# driver-power-stage.net
KiCad netlist of a schematic drawn in Altium Designer
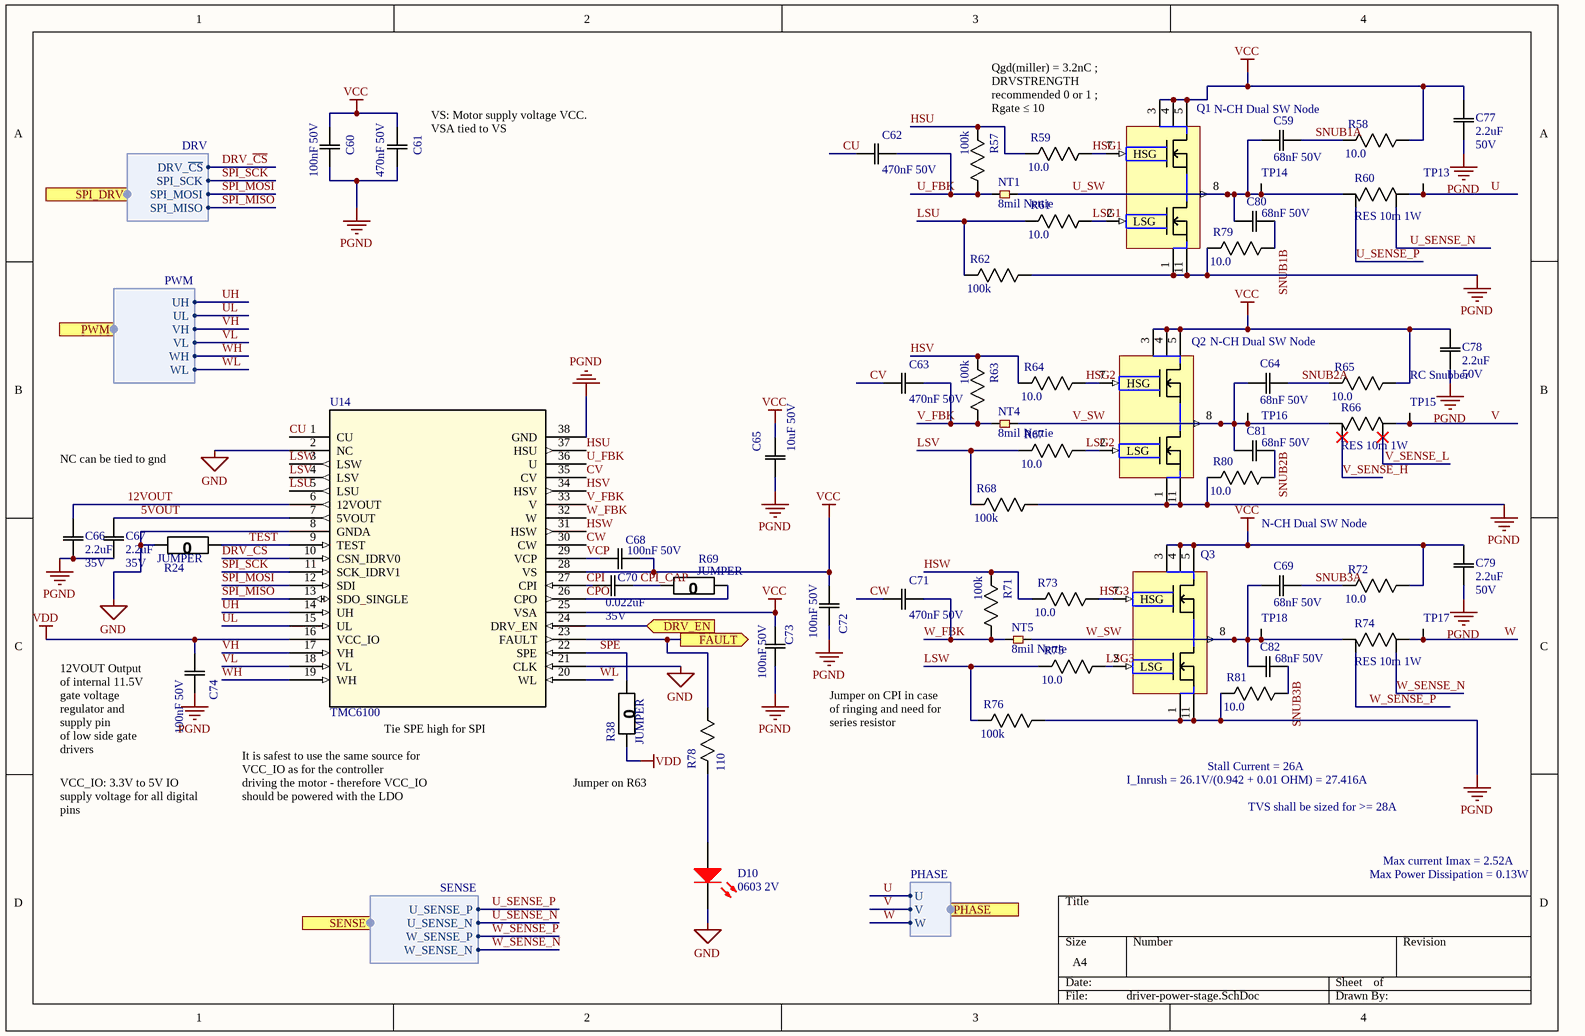
[diagram p0: driver-power-stage.SchDoc]

(export (version "E")
  (design (tool "Eeschema 10.0.6"))
  (components
    (comp (ref "C59")
      (value "68nF 50V")
      (footprint "0603")
      (description "Default Symbol for Capacitors")
      (fields (field (name "PART NUMBER") "CAP 0.068uF 50V") (field (name "TOLERANCE") "10%"))
      (libsource (lib "capacitor_library") (part "CAP_Default"))
    )
    (comp (ref "C60")
      (value "100nF 50V")
      (footprint "0603")
      (description "Default Symbol for Capacitors")
      (fields (field (name "TOLERANCE") "10%") (field (name "PART NUMBER") "CAP 100nF 50V"))
      (libsource (lib "capacitor_library") (part "CAP_Default"))
    )
    (comp (ref "C61")
      (value "470nF 50V")
      (footprint "0603")
      (description "Default Symbol for Capacitors")
      (fields (field (name "TOLERANCE") "10%") (field (name "PART NUMBER") "CAP 470nF 50V"))
      (libsource (lib "capacitor_library") (part "CAP_Default"))
    )
    (comp (ref "C62")
      (value "470nF 50V")
      (footprint "0603")
      (description "Default Symbol for Capacitors")
      (fields (field (name "TOLERANCE") "10%") (field (name "PART NUMBER") "CAP 470nF 50V"))
      (libsource (lib "capacitor_library") (part "CAP_Default"))
    )
    (comp (ref "C63")
      (value "470nF 50V")
      (footprint "0603")
      (description "Default Symbol for Capacitors")
      (fields (field (name "TOLERANCE") "10%") (field (name "PART NUMBER") "CAP 470nF 50V"))
      (libsource (lib "capacitor_library") (part "CAP_Default"))
    )
    (comp (ref "C64")
      (value "68nF 50V")
      (footprint "0603")
      (description "Default Symbol for Capacitors")
      (fields (field (name "PART NUMBER") "CAP 0.068uF 50V") (field (name "TOLERANCE") "10%"))
      (libsource (lib "capacitor_library") (part "CAP_Default"))
    )
    (comp (ref "C65")
      (value "10uF 50V")
      (footprint "0805")
      (description "Default Symbol for Capacitors")
      (fields (field (name "TOLERANCE") "10%") (field (name "PART NUMBER") "CAP 10uF 50V"))
      (libsource (lib "capacitor_library") (part "CAP_Default"))
    )
    (comp (ref "C66")
      (value "2.2uF")
      (footprint "0603")
      (description "Default Symbol for Capacitors")
      (fields
        (field (name "TOLERANCE") "10%")
        (field (name "RATING") "35V")
        (field (name "PART NUMBER") "CAP 2.2uF 35V")
      )
      (libsource (lib "capacitor_library") (part "CAP_Default"))
    )
    (comp (ref "C67")
      (value "2.2uF")
      (footprint "0603")
      (description "Default Symbol for Capacitors")
      (fields
        (field (name "TOLERANCE") "10%")
        (field (name "RATING") "35V")
        (field (name "PART NUMBER") "CAP 2.2uF 35V")
      )
      (libsource (lib "capacitor_library") (part "CAP_Default"))
    )
    (comp (ref "C68")
      (value "100nF 50V")
      (footprint "0603")
      (description "Default Symbol for Capacitors")
      (fields (field (name "TOLERANCE") "10%") (field (name "PART NUMBER") "CAP 100nF 50V"))
      (libsource (lib "capacitor_library") (part "CAP_Default"))
    )
    (comp (ref "C69")
      (value "68nF 50V")
      (footprint "0603")
      (description "Default Symbol for Capacitors")
      (fields (field (name "PART NUMBER") "CAP 0.068uF 50V") (field (name "TOLERANCE") "10%"))
      (libsource (lib "capacitor_library") (part "CAP_Default"))
    )
    (comp (ref "C70")
      (value "0.022uF")
      (footprint "0603")
      (description "Default Symbol for Capacitors")
      (fields
        (field (name "TOLERANCE") "10%")
        (field (name "RATING") "35V")
        (field (name "PART NUMBER") "CAP 0.022uF 35V")
      )
      (libsource (lib "capacitor_library") (part "CAP_Default"))
    )
    (comp (ref "C71")
      (value "470nF 50V")
      (footprint "0603")
      (description "Default Symbol for Capacitors")
      (fields (field (name "TOLERANCE") "10%") (field (name "PART NUMBER") "CAP 470nF 50V"))
      (libsource (lib "capacitor_library") (part "CAP_Default"))
    )
    (comp (ref "C72")
      (value "100nF 50V")
      (footprint "0603")
      (description "Default Symbol for Capacitors")
      (fields (field (name "TOLERANCE") "10%") (field (name "PART NUMBER") "CAP 100nF 50V"))
      (libsource (lib "capacitor_library") (part "CAP_Default"))
    )
    (comp (ref "C73")
      (value "100nF 50V")
      (footprint "0603")
      (description "Default Symbol for Capacitors")
      (fields (field (name "TOLERANCE") "10%") (field (name "PART NUMBER") "CAP 100nF 50V"))
      (libsource (lib "capacitor_library") (part "CAP_Default"))
    )
    (comp (ref "C74")
      (value "100nF 50V")
      (footprint "0603")
      (description "Default Symbol for Capacitors")
      (fields (field (name "TOLERANCE") "10%") (field (name "PART NUMBER") "CAP 100nF 50V"))
      (libsource (lib "capacitor_library") (part "CAP_Default"))
    )
    (comp (ref "C77")
      (value "2.2uF")
      (footprint "0603")
      (description "CAP CER 2.2UF 50V X5R 0603/0805")
      (fields
        (field (name "TOLERANCE") "10%")
        (field (name "RATING") "50V")
        (field (name "PART NUMBER") "CAP 2.2uF 50V")
      )
      (libsource (lib "capacitor_library") (part "CAP 2.2uF 50V"))
    )
    (comp (ref "C78")
      (value "2.2uF")
      (footprint "0603")
      (description "CAP CER 2.2UF 50V X5R 0603/0805")
      (fields
        (field (name "TOLERANCE") "10%")
        (field (name "RATING") "50V")
        (field (name "PART NUMBER") "CAP 2.2uF 50V")
      )
      (libsource (lib "capacitor_library") (part "CAP 2.2uF 50V"))
    )
    (comp (ref "C79")
      (value "2.2uF")
      (footprint "0603")
      (description "CAP CER 2.2UF 50V X5R 0603/0805")
      (fields
        (field (name "TOLERANCE") "10%")
        (field (name "RATING") "50V")
        (field (name "PART NUMBER") "CAP 2.2uF 50V")
      )
      (libsource (lib "capacitor_library") (part "CAP 2.2uF 50V"))
    )
    (comp (ref "C80")
      (value "68nF 50V")
      (footprint "0603")
      (description "Default Symbol for Capacitors")
      (fields (field (name "PART NUMBER") "CAP 0.068uF 50V") (field (name "TOLERANCE") "10%"))
      (libsource (lib "capacitor_library") (part "CAP_Default"))
    )
    (comp (ref "C81")
      (value "68nF 50V")
      (footprint "0603")
      (description "Default Symbol for Capacitors")
      (fields (field (name "PART NUMBER") "CAP 0.068uF 50V") (field (name "TOLERANCE") "10%"))
      (libsource (lib "capacitor_library") (part "CAP_Default"))
    )
    (comp (ref "C82")
      (value "68nF 50V")
      (footprint "0603")
      (description "Default Symbol for Capacitors")
      (fields (field (name "PART NUMBER") "CAP 0.068uF 50V") (field (name "TOLERANCE") "10%"))
      (libsource (lib "capacitor_library") (part "CAP_Default"))
    )
    (comp (ref "D10")
      (value "0603 2V")
      (footprint "0603 - LED2")
      (description "0603 red led alingap 631nm-639nm water clear 18-180mcd 130d")
      (fields (field (name "PART NUMBER") "LED RED SMD 0603"))
      (libsource (lib "Diode_Library") (part "LED RED SMD 0603"))
    )
    (comp (ref "NT1")
      (value "8mil Nettie")
      (footprint "NT_8mil")
      (description "74LVC Series 5.5 V SMT 2-Channel Analog Multiplexer/Demultiplexer - TSSOP-8")
      (fields (field (name "PART NUMBER") "NT_8"))
      (libsource (lib "IC_Library") (part "NT_8"))
    )
    (comp (ref "NT4")
      (value "8mil Nettie")
      (footprint "NT_8mil")
      (description "74LVC Series 5.5 V SMT 2-Channel Analog Multiplexer/Demultiplexer - TSSOP-8")
      (fields (field (name "PART NUMBER") "NT_8"))
      (libsource (lib "IC_Library") (part "NT_8"))
    )
    (comp (ref "NT5")
      (value "8mil Nettie")
      (footprint "NT_8mil")
      (description "74LVC Series 5.5 V SMT 2-Channel Analog Multiplexer/Demultiplexer - TSSOP-8")
      (fields (field (name "PART NUMBER") "NT_8"))
      (libsource (lib "IC_Library") (part "NT_8"))
    )
    (comp (ref "Q1")
      (value "N-CH Dual SW Node")
      (footprint "12-PowerWQFN")
      (description "MOSFET N+N COMMON PHASE SW 40V 60A")
      (fields (field (name "PART NUMBER") "MOSFET N-CH DUAL NTTFD4D0N04HLTWG"))
      (libsource (lib "Transistor_Library") (part "MOSFET N-CH DUAL NTTFD4D0N04HLTWG"))
    )
    (comp (ref "Q2")
      (value "N-CH Dual SW Node")
      (footprint "12-PowerWQFN")
      (description "MOSFET N+N COMMON PHASE SW 40V 60A")
      (fields (field (name "PART NUMBER") "MOSFET N-CH DUAL NTTFD4D0N04HLTWG"))
      (libsource (lib "Transistor_Library") (part "MOSFET N-CH DUAL NTTFD4D0N04HLTWG"))
    )
    (comp (ref "Q3")
      (value "N-CH Dual SW Node")
      (footprint "12-PowerWQFN")
      (description "MOSFET N+N COMMON PHASE SW 40V 60A")
      (fields (field (name "PART NUMBER") "MOSFET N-CH DUAL NTTFD4D0N04HLTWG"))
      (libsource (lib "Transistor_Library") (part "MOSFET N-CH DUAL NTTFD4D0N04HLTWG"))
    )
    (comp (ref "R24")
      (value "JUMPER")
      (footprint "0603")
      (description "RES SMD 0 OHM JUMPER GENERIC 0805")
      (fields (field (name "PART NUMBER") "RES 0 JUMPER"))
      (libsource (lib "Resistor_Library") (part "RES 0 JUMPER"))
    )
    (comp (ref "R38")
      (value "JUMPER")
      (footprint "0603")
      (description "RES SMD 0 OHM JUMPER GENERIC 0805")
      (fields (field (name "PART NUMBER") "RES 0 JUMPER"))
      (libsource (lib "Resistor_Library") (part "RES 0 JUMPER"))
    )
    (comp (ref "R57")
      (value "100k")
      (footprint "0603")
      (description "RES SMD 100K OHM 5% 1/8W 0805")
      (fields (field (name "TOLERANCE") "5%") (field (name "PART NUMBER") "RES 100k 1/8W 5%"))
      (libsource (lib "") (part "RES_DEFAULT_1"))
    )
    (comp (ref "R58")
      (value "10.0")
      (footprint "0603")
      (description "Default Resistor Symbol")
      (fields (field (name "TOLERANCE") "1%") (field (name "PART NUMBER") "RES 10.0 1/8W - 1%"))
      (libsource (lib "Resistor_Library") (part "RES_DEFAULT"))
    )
    (comp (ref "R59")
      (value "10.0")
      (footprint "0603")
      (description "Default Resistor Symbol")
      (fields (field (name "TOLERANCE") "1%") (field (name "PART NUMBER") "RES 10.0 1/8W - 1%"))
      (libsource (lib "") (part "RES_DEFAULT_1"))
    )
    (comp (ref "R60")
      (value "RES 10m 1W")
      (footprint "1206 - Current Sense")
      (description "RES SMD 0.01 OHM 1% 1W 1206")
      (fields (field (name "TOLERANCE") "1%"))
      (libsource (lib "Resistor_Library") (part "RES 10m 1W"))
    )
    (comp (ref "R61")
      (value "10.0")
      (footprint "0603")
      (description "Default Resistor Symbol")
      (fields (field (name "TOLERANCE") "1%") (field (name "PART NUMBER") "RES 10.0 1/8W - 1%"))
      (libsource (lib "") (part "RES_DEFAULT_1"))
    )
    (comp (ref "R62")
      (value "100k")
      (footprint "0603")
      (description "RES SMD 100K OHM 5% 1/8W 0805")
      (fields (field (name "TOLERANCE") "5%") (field (name "PART NUMBER") "RES 100k 1/8W 5%"))
      (libsource (lib "") (part "RES_DEFAULT_1"))
    )
    (comp (ref "R63")
      (value "100k")
      (footprint "0603")
      (description "RES SMD 100K OHM 5% 1/8W 0805")
      (fields (field (name "TOLERANCE") "5%") (field (name "PART NUMBER") "RES 100k 1/8W 5%"))
      (libsource (lib "") (part "RES_DEFAULT_1"))
    )
    (comp (ref "R64")
      (value "10.0")
      (footprint "0603")
      (description "Default Resistor Symbol")
      (fields (field (name "TOLERANCE") "1%") (field (name "PART NUMBER") "RES 10.0 1/8W - 1%"))
      (libsource (lib "Resistor_Library") (part "RES_DEFAULT"))
    )
    (comp (ref "R65")
      (value "10.0")
      (footprint "0603")
      (description "Default Resistor Symbol")
      (fields (field (name "TOLERANCE") "1%") (field (name "PART NUMBER") "RES 10.0 1/8W - 1%"))
      (libsource (lib "Resistor_Library") (part "RES_DEFAULT"))
    )
    (comp (ref "R66")
      (value "RES 10m 1W")
      (footprint "1206 - Current Sense")
      (description "RES SMD 0.01 OHM 1% 1W 1206")
      (fields (field (name "TOLERANCE") "1%"))
      (libsource (lib "Resistor_Library") (part "RES 10m 1W"))
    )
    (comp (ref "R67")
      (value "10.0")
      (footprint "0603")
      (description "Default Resistor Symbol")
      (fields (field (name "TOLERANCE") "1%") (field (name "PART NUMBER") "RES 10.0 1/8W - 1%"))
      (libsource (lib "") (part "RES_DEFAULT_1"))
    )
    (comp (ref "R68")
      (value "100k")
      (footprint "0603")
      (description "RES SMD 100K OHM 5% 1/8W 0805")
      (fields (field (name "TOLERANCE") "5%") (field (name "PART NUMBER") "RES 100k 1/8W 5%"))
      (libsource (lib "") (part "RES_DEFAULT_1"))
    )
    (comp (ref "R69")
      (value "JUMPER")
      (footprint "0603")
      (description "RES SMD 0 OHM JUMPER GENERIC 0805")
      (fields (field (name "PART NUMBER") "RES 0 JUMPER"))
      (libsource (lib "Resistor_Library") (part "RES 0 JUMPER"))
    )
    (comp (ref "R71")
      (value "100k")
      (footprint "0603")
      (description "RES SMD 100K OHM 5% 1/8W 0805")
      (fields (field (name "TOLERANCE") "5%") (field (name "PART NUMBER") "RES 100k 1/8W 5%"))
      (libsource (lib "") (part "RES_DEFAULT_1"))
    )
    (comp (ref "R72")
      (value "10.0")
      (footprint "0603")
      (description "Default Resistor Symbol")
      (fields (field (name "TOLERANCE") "1%") (field (name "PART NUMBER") "RES 10.0 1/8W - 1%"))
      (libsource (lib "Resistor_Library") (part "RES_DEFAULT"))
    )
    (comp (ref "R73")
      (value "10.0")
      (footprint "0603")
      (description "Default Resistor Symbol")
      (fields (field (name "TOLERANCE") "1%") (field (name "PART NUMBER") "RES 10.0 1/8W - 1%"))
      (libsource (lib "Resistor_Library") (part "RES_DEFAULT"))
    )
    (comp (ref "R74")
      (value "RES 10m 1W")
      (footprint "1206 - Current Sense")
      (description "RES SMD 0.01 OHM 1% 1W 1206")
      (fields (field (name "TOLERANCE") "1%"))
      (libsource (lib "Resistor_Library") (part "RES 10m 1W"))
    )
    (comp (ref "R75")
      (value "10.0")
      (footprint "0603")
      (description "Default Resistor Symbol")
      (fields (field (name "TOLERANCE") "1%") (field (name "PART NUMBER") "RES 10.0 1/8W - 1%"))
      (libsource (lib "Resistor_Library") (part "RES_DEFAULT"))
    )
    (comp (ref "R76")
      (value "100k")
      (footprint "0603")
      (description "RES SMD 100K OHM 5% 1/8W 0805")
      (fields (field (name "TOLERANCE") "5%") (field (name "PART NUMBER") "RES 100k 1/8W 5%"))
      (libsource (lib "") (part "RES_DEFAULT_1"))
    )
    (comp (ref "R78")
      (value "110")
      (footprint "0603")
      (description "Default Resistor Symbol")
      (fields (field (name "TOLERANCE") "1%") (field (name "PART NUMBER") "RES 110.0 1/8W - 1%"))
      (libsource (lib "") (part "RES_DEFAULT_1"))
    )
    (comp (ref "R79")
      (value "10.0")
      (footprint "0603")
      (description "Default Resistor Symbol")
      (fields (field (name "TOLERANCE") "1%") (field (name "PART NUMBER") "RES 10.0 1/8W - 1%"))
      (libsource (lib "") (part "RES_DEFAULT_1"))
    )
    (comp (ref "R80")
      (value "10.0")
      (footprint "0603")
      (description "Default Resistor Symbol")
      (fields (field (name "TOLERANCE") "1%") (field (name "PART NUMBER") "RES 10.0 1/8W - 1%"))
      (libsource (lib "") (part "RES_DEFAULT_1"))
    )
    (comp (ref "R81")
      (value "10.0")
      (footprint "0603")
      (description "Default Resistor Symbol")
      (fields (field (name "TOLERANCE") "1%") (field (name "PART NUMBER") "RES 10.0 1/8W - 1%"))
      (libsource (lib "") (part "RES_DEFAULT_1"))
    )
    (comp (ref "TP13")
      (value "U_SL")
      (footprint "TP")
      (fields (field (name "PART NUMBER") "Test Point (Via)"))
      (libsource (lib "IC_Library") (part "Test Point (Via)"))
    )
    (comp (ref "TP14")
      (value "U_SH")
      (footprint "TP")
      (fields (field (name "PART NUMBER") "Test Point (Via)"))
      (libsource (lib "IC_Library") (part "Test Point (Via)"))
    )
    (comp (ref "TP15")
      (value "V_SL")
      (footprint "TP")
      (fields (field (name "PART NUMBER") "Test Point (Via)"))
      (libsource (lib "IC_Library") (part "Test Point (Via)"))
    )
    (comp (ref "TP16")
      (value "V_SH")
      (footprint "TP")
      (fields (field (name "PART NUMBER") "Test Point (Via)"))
      (libsource (lib "IC_Library") (part "Test Point (Via)"))
    )
    (comp (ref "TP17")
      (value "W_SL")
      (footprint "TP")
      (fields (field (name "PART NUMBER") "Test Point (Via)"))
      (libsource (lib "IC_Library") (part "Test Point (Via)"))
    )
    (comp (ref "TP18")
      (value "W_SH")
      (footprint "TP")
      (fields (field (name "PART NUMBER") "Test Point (Via)"))
      (libsource (lib "IC_Library") (part "Test Point (Via)"))
    )
    (comp (ref "U14")
      (value "TMC6100")
      (footprint "QFN50P700X700X85_HS-38N")
      (description "GATE DRIVER IC 8-60V QFN37")
      (libsource (lib "IC_Library") (part "TMC6100"))
    )
  )
  (nets
    (net (code "5") (name "/5VOUT") (class "Default")
      (node (ref "C67") (pin "2") (pinfunction "C2_2") (pintype "passive"))
      (node (ref "U14") (pin "7") (pinfunction "5VOUT_7") (pintype "output"))
    )
    (net (code "6") (name "/12VOUT") (class "Default")
      (node (ref "C66") (pin "2") (pinfunction "C2_2") (pintype "passive"))
      (node (ref "U14") (pin "6") (pinfunction "12VOUT_6") (pintype "output"))
    )
    (net (code "7") (name "/CPI") (class "Default")
      (node (ref "C70") (pin "1") (pinfunction "C1_1") (pintype "passive"))
      (node (ref "U14") (pin "27") (pinfunction "CPI_27") (pintype "input"))
    )
    (net (code "8") (name "/CPI_CAP") (class "Default")
      (node (ref "C70") (pin "2") (pinfunction "C2_2") (pintype "passive"))
      (node (ref "R69") (pin "2") (pinfunction "R2_2") (pintype "passive"))
    )
    (net (code "9") (name "/CPO") (class "Default")
      (node (ref "R69") (pin "1") (pinfunction "R1_1") (pintype "passive"))
      (node (ref "U14") (pin "26") (pinfunction "CPO_26") (pintype "output"))
    )
    (net (code "10") (name "/CU") (class "Default")
      (node (ref "C62") (pin "1") (pinfunction "C1_1") (pintype "passive"))
      (node (ref "U14") (pin "1") (pinfunction "CU_1") (pintype "passive"))
    )
    (net (code "11") (name "/CV") (class "Default")
      (node (ref "C63") (pin "1") (pinfunction "C1_1") (pintype "passive"))
      (node (ref "U14") (pin "35") (pinfunction "CV_35") (pintype "passive"))
    )
    (net (code "12") (name "/CW") (class "Default")
      (node (ref "C71") (pin "1") (pinfunction "C1_1") (pintype "passive"))
      (node (ref "U14") (pin "30") (pinfunction "CW_30") (pintype "passive"))
    )
    (net (code "13") (name "/DRV_EN") (class "Default")
      (node (ref "U14") (pin "24") (pinfunction "DRV_EN_24") (pintype "input"))
    )
    (net (code "14") (name "/DRV_~{CS}") (class "Default")
      (node (ref "U14") (pin "10") (pinfunction "CSN_IDRV0_10") (pintype "input"))
    )
    (net (code "15") (name "/FAULT") (class "Default")
      (node (ref "R78") (pin "1") (pinfunction "R1_1") (pintype "passive"))
      (node (ref "U14") (pin "23") (pinfunction "FAULT_23") (pintype "output"))
    )
    (net (code "16") (name "/HSG1") (class "Default")
      (node (ref "Q1") (pin "7") (pinfunction "HSG_7") (pintype "input"))
      (node (ref "R59") (pin "1") (pinfunction "R1_1") (pintype "passive"))
    )
    (net (code "17") (name "/HSG2") (class "Default")
      (node (ref "Q2") (pin "7") (pinfunction "HSG_7") (pintype "input"))
      (node (ref "R64") (pin "1") (pinfunction "R1_1") (pintype "passive"))
    )
    (net (code "18") (name "/HSG3") (class "Default")
      (node (ref "Q3") (pin "7") (pinfunction "HSG_7") (pintype "input"))
      (node (ref "R73") (pin "1") (pinfunction "R1_1") (pintype "passive"))
    )
    (net (code "19") (name "/HSU") (class "Default")
      (node (ref "R57") (pin "2") (pinfunction "R2_2") (pintype "passive"))
      (node (ref "R59") (pin "2") (pinfunction "R2_2") (pintype "passive"))
      (node (ref "U14") (pin "37") (pinfunction "HSU_37") (pintype "output"))
    )
    (net (code "20") (name "/HSV") (class "Default")
      (node (ref "R63") (pin "2") (pinfunction "R2_2") (pintype "passive"))
      (node (ref "R64") (pin "2") (pinfunction "R2_2") (pintype "passive"))
      (node (ref "U14") (pin "34") (pinfunction "HSV_34") (pintype "output"))
    )
    (net (code "21") (name "/HSW") (class "Default")
      (node (ref "R71") (pin "2") (pinfunction "R2_2") (pintype "passive"))
      (node (ref "R73") (pin "2") (pinfunction "R2_2") (pintype "passive"))
      (node (ref "U14") (pin "31") (pinfunction "HSW_31") (pintype "output"))
    )
    (net (code "22") (name "/LSG1") (class "Default")
      (node (ref "Q1") (pin "2") (pinfunction "LSG_2") (pintype "input"))
      (node (ref "R61") (pin "1") (pinfunction "R1_1") (pintype "passive"))
    )
    (net (code "23") (name "/LSG2") (class "Default")
      (node (ref "Q2") (pin "2") (pinfunction "LSG_2") (pintype "input"))
      (node (ref "R67") (pin "1") (pinfunction "R1_1") (pintype "passive"))
    )
    (net (code "24") (name "/LSG3") (class "Default")
      (node (ref "Q3") (pin "2") (pinfunction "LSG_2") (pintype "input"))
      (node (ref "R75") (pin "1") (pinfunction "R1_1") (pintype "passive"))
    )
    (net (code "25") (name "/LSU") (class "Default")
      (node (ref "R61") (pin "2") (pinfunction "R2_2") (pintype "passive"))
      (node (ref "R62") (pin "2") (pinfunction "R2_2") (pintype "passive"))
      (node (ref "U14") (pin "5") (pinfunction "LSU_5") (pintype "output"))
    )
    (net (code "26") (name "/LSV") (class "Default")
      (node (ref "R67") (pin "2") (pinfunction "R2_2") (pintype "passive"))
      (node (ref "R68") (pin "2") (pinfunction "R2_2") (pintype "passive"))
      (node (ref "U14") (pin "4") (pinfunction "LSV_4") (pintype "output"))
    )
    (net (code "27") (name "/LSW") (class "Default")
      (node (ref "R75") (pin "2") (pinfunction "R2_2") (pintype "passive"))
      (node (ref "R76") (pin "2") (pinfunction "R2_2") (pintype "passive"))
      (node (ref "U14") (pin "3") (pinfunction "LSW_3") (pintype "output"))
    )
    (net (code "28") (name "/SNUB1A") (class "Default")
      (node (ref "C59") (pin "2") (pinfunction "C2_2") (pintype "passive"))
      (node (ref "R58") (pin "2") (pinfunction "R2_2") (pintype "passive"))
    )
    (net (code "29") (name "/SNUB1B") (class "Default")
      (node (ref "C80") (pin "2") (pinfunction "C2_2") (pintype "passive"))
      (node (ref "R79") (pin "1") (pinfunction "R1_1") (pintype "passive"))
    )
    (net (code "30") (name "/SNUB2A") (class "Default")
      (node (ref "C64") (pin "2") (pinfunction "C2_2") (pintype "passive"))
      (node (ref "R65") (pin "2") (pinfunction "R2_2") (pintype "passive"))
    )
    (net (code "31") (name "/SNUB2B") (class "Default")
      (node (ref "C81") (pin "2") (pinfunction "C2_2") (pintype "passive"))
      (node (ref "R80") (pin "1") (pinfunction "R1_1") (pintype "passive"))
    )
    (net (code "32") (name "/SNUB3A") (class "Default")
      (node (ref "C69") (pin "2") (pinfunction "C2_2") (pintype "passive"))
      (node (ref "R72") (pin "2") (pinfunction "R2_2") (pintype "passive"))
    )
    (net (code "33") (name "/SNUB3B") (class "Default")
      (node (ref "C82") (pin "2") (pinfunction "C2_2") (pintype "passive"))
      (node (ref "R81") (pin "1") (pinfunction "R1_1") (pintype "passive"))
    )
    (net (code "34") (name "/SPE") (class "Default")
      (node (ref "R38") (pin "1") (pinfunction "R1_1") (pintype "passive"))
      (node (ref "U14") (pin "22") (pinfunction "SPE_22") (pintype "input"))
    )
    (net (code "35") (name "/SPI_MISO") (class "Default")
      (node (ref "U14") (pin "13") (pinfunction "SDO_SINGLE_13") (pintype "bidirectional"))
    )
    (net (code "36") (name "/SPI_MOSI") (class "Default")
      (node (ref "U14") (pin "12") (pinfunction "SDI_12") (pintype "input"))
    )
    (net (code "37") (name "/SPI_SCK") (class "Default")
      (node (ref "U14") (pin "11") (pinfunction "SCK_IDRV1_11") (pintype "input"))
    )
    (net (code "38") (name "/TEST") (class "Default")
      (node (ref "R24") (pin "1") (pinfunction "R1_1") (pintype "passive"))
      (node (ref "U14") (pin "9") (pinfunction "TEST_9") (pintype "input"))
    )
    (net (code "39") (name "/U") (class "Default")
      (node (ref "R60") (pin "1") (pinfunction "R1_1") (pintype "passive"))
      (node (ref "TP13") (pin "1") (pinfunction "1_1") (pintype "passive"))
    )
    (net (code "40") (name "/UH") (class "Default")
      (node (ref "U14") (pin "14") (pinfunction "UH_14") (pintype "input"))
    )
    (net (code "41") (name "/UL") (class "Default")
      (node (ref "U14") (pin "15") (pinfunction "UL_15") (pintype "input"))
    )
    (net (code "42") (name "/U_FBK") (class "Default")
      (node (ref "C62") (pin "2") (pinfunction "C2_2") (pintype "passive"))
      (node (ref "NT1") (pin "2") (pinfunction "2_2") (pintype "passive"))
      (node (ref "R57") (pin "1") (pinfunction "R1_1") (pintype "passive"))
      (node (ref "U14") (pin "36") (pinfunction "U_36") (pintype "passive"))
    )
    (net (code "43") (name "/U_SENSE_N") (class "Default")
      (node (ref "R60") (pin "S1") (pinfunction "S1_S1") (pintype "passive"))
    )
    (net (code "44") (name "/U_SENSE_P") (class "Default")
      (node (ref "R60") (pin "S2") (pinfunction "S2_S2") (pintype "passive"))
    )
    (net (code "45") (name "/U_SW") (class "Default")
      (node (ref "C59") (pin "1") (pinfunction "C1_1") (pintype "passive"))
      (node (ref "C80") (pin "1") (pinfunction "C1_1") (pintype "passive"))
      (node (ref "NT1") (pin "1") (pinfunction "1_1") (pintype "passive"))
      (node (ref "Q1") (pin "8") (pinfunction "SW_8") (pintype "output"))
      (node (ref "R60") (pin "2") (pinfunction "R2_2") (pintype "passive"))
      (node (ref "TP14") (pin "1") (pinfunction "1_1") (pintype "passive"))
    )
    (net (code "46") (name "/V") (class "Default")
      (node (ref "R66") (pin "1") (pinfunction "R1_1") (pintype "passive"))
      (node (ref "TP15") (pin "1") (pinfunction "1_1") (pintype "passive"))
    )
    (net (code "47") (name "/VCP") (class "Default")
      (node (ref "C68") (pin "1") (pinfunction "C1_1") (pintype "passive"))
      (node (ref "U14") (pin "29") (pinfunction "VCP_29") (pintype "power_in"))
    )
    (net (code "48") (name "/VH") (class "Default")
      (node (ref "U14") (pin "17") (pinfunction "VH_17") (pintype "input"))
    )
    (net (code "49") (name "/VL") (class "Default")
      (node (ref "U14") (pin "18") (pinfunction "VL_18") (pintype "input"))
    )
    (net (code "50") (name "/V_FBK") (class "Default")
      (node (ref "C63") (pin "2") (pinfunction "C2_2") (pintype "passive"))
      (node (ref "NT4") (pin "2") (pinfunction "2_2") (pintype "passive"))
      (node (ref "R63") (pin "1") (pinfunction "R1_1") (pintype "passive"))
      (node (ref "U14") (pin "33") (pinfunction "V_33") (pintype "passive"))
    )
    (net (code "51") (name "/V_SENSE_H") (class "Default")
      (node (ref "R66") (pin "S2") (pinfunction "S2_S2") (pintype "passive+no_connect"))
    )
    (net (code "52") (name "/V_SENSE_L") (class "Default")
      (node (ref "R66") (pin "S1") (pinfunction "S1_S1") (pintype "passive+no_connect"))
    )
    (net (code "53") (name "/V_SW") (class "Default")
      (node (ref "C64") (pin "1") (pinfunction "C1_1") (pintype "passive"))
      (node (ref "C81") (pin "1") (pinfunction "C1_1") (pintype "passive"))
      (node (ref "NT4") (pin "1") (pinfunction "1_1") (pintype "passive"))
      (node (ref "Q2") (pin "8") (pinfunction "SW_8") (pintype "output"))
      (node (ref "R66") (pin "2") (pinfunction "R2_2") (pintype "passive"))
      (node (ref "TP16") (pin "1") (pinfunction "1_1") (pintype "passive"))
    )
    (net (code "54") (name "/W") (class "Default")
      (node (ref "R74") (pin "1") (pinfunction "R1_1") (pintype "passive"))
      (node (ref "TP17") (pin "1") (pinfunction "1_1") (pintype "passive"))
    )
    (net (code "55") (name "/WH") (class "Default")
      (node (ref "U14") (pin "19") (pinfunction "WH_19") (pintype "input"))
    )
    (net (code "56") (name "/WL") (class "Default")
      (node (ref "U14") (pin "20") (pinfunction "WL_20") (pintype "input"))
    )
    (net (code "57") (name "/W_FBK") (class "Default")
      (node (ref "C71") (pin "2") (pinfunction "C2_2") (pintype "passive"))
      (node (ref "NT5") (pin "2") (pinfunction "2_2") (pintype "passive"))
      (node (ref "R71") (pin "1") (pinfunction "R1_1") (pintype "passive"))
      (node (ref "U14") (pin "32") (pinfunction "W_32") (pintype "passive"))
    )
    (net (code "58") (name "/W_SENSE_N") (class "Default")
      (node (ref "R74") (pin "S1") (pinfunction "S1_S1") (pintype "passive"))
    )
    (net (code "59") (name "/W_SENSE_P") (class "Default")
      (node (ref "R74") (pin "S2") (pinfunction "S2_S2") (pintype "passive"))
    )
    (net (code "60") (name "/W_SW") (class "Default")
      (node (ref "C69") (pin "1") (pinfunction "C1_1") (pintype "passive"))
      (node (ref "C82") (pin "1") (pinfunction "C1_1") (pintype "passive"))
      (node (ref "NT5") (pin "1") (pinfunction "1_1") (pintype "passive"))
      (node (ref "Q3") (pin "8") (pinfunction "SW_8") (pintype "output"))
      (node (ref "R74") (pin "2") (pinfunction "R2_2") (pintype "passive"))
      (node (ref "TP18") (pin "1") (pinfunction "1_1") (pintype "passive"))
    )
    (net (code "65") (name "GND") (class "Default")
      (node (ref "D10") (pin "2") (pinfunction "K_2") (pintype "passive"))
      (node (ref "R24") (pin "2") (pinfunction "R2_2") (pintype "passive"))
      (node (ref "U14") (pin "2") (pinfunction "NC_2") (pintype "passive"))
      (node (ref "U14") (pin "21") (pinfunction "CLK_21") (pintype "input"))
      (node (ref "U14") (pin "8") (pinfunction "GNDA_8") (pintype "power_in"))
    )
    (net (code "66") (name "Net-(D10-A)") (class "Default")
      (node (ref "D10") (pin "1") (pinfunction "A_1") (pintype "passive"))
      (node (ref "R78") (pin "2") (pinfunction "R2_2") (pintype "passive"))
    )
    (net (code "67") (name "PGND") (class "Default")
      (node (ref "C60") (pin "2") (pinfunction "C2_2") (pintype "passive"))
      (node (ref "C61") (pin "2") (pinfunction "C2_2") (pintype "passive"))
      (node (ref "C65") (pin "1") (pinfunction "C1_1") (pintype "passive"))
      (node (ref "C66") (pin "1") (pinfunction "C1_1") (pintype "passive"))
      (node (ref "C67") (pin "1") (pinfunction "C1_1") (pintype "passive"))
      (node (ref "C72") (pin "2") (pinfunction "C2_2") (pintype "passive"))
      (node (ref "C73") (pin "2") (pinfunction "C2_2") (pintype "passive"))
      (node (ref "C74") (pin "2") (pinfunction "C2_2") (pintype "passive"))
      (node (ref "C77") (pin "1") (pinfunction "C1_1") (pintype "passive"))
      (node (ref "C78") (pin "1") (pinfunction "C1_1") (pintype "passive"))
      (node (ref "C79") (pin "1") (pinfunction "C1_1") (pintype "passive"))
      (node (ref "Q1") (pin "1") (pinfunction "GND_1") (pintype "power_in"))
      (node (ref "Q1") (pin "11") (pinfunction "GND_11") (pintype "power_in"))
      (node (ref "Q2") (pin "1") (pinfunction "GND_1") (pintype "power_in"))
      (node (ref "Q2") (pin "11") (pinfunction "GND_11") (pintype "power_in"))
      (node (ref "Q3") (pin "1") (pinfunction "GND_1") (pintype "power_in"))
      (node (ref "Q3") (pin "11") (pinfunction "GND_11") (pintype "power_in"))
      (node (ref "R62") (pin "1") (pinfunction "R1_1") (pintype "passive"))
      (node (ref "R68") (pin "1") (pinfunction "R1_1") (pintype "passive"))
      (node (ref "R76") (pin "1") (pinfunction "R1_1") (pintype "passive"))
      (node (ref "R79") (pin "2") (pinfunction "R2_2") (pintype "passive"))
      (node (ref "R80") (pin "2") (pinfunction "R2_2") (pintype "passive"))
      (node (ref "R81") (pin "2") (pinfunction "R2_2") (pintype "passive"))
      (node (ref "U14") (pin "38") (pinfunction "GND_38") (pintype "passive"))
    )
    (net (code "68") (name "VCC") (class "Default")
      (node (ref "C60") (pin "1") (pinfunction "C1_1") (pintype "passive"))
      (node (ref "C61") (pin "1") (pinfunction "C1_1") (pintype "passive"))
      (node (ref "C65") (pin "2") (pinfunction "C2_2") (pintype "passive"))
      (node (ref "C68") (pin "2") (pinfunction "C2_2") (pintype "passive"))
      (node (ref "C72") (pin "1") (pinfunction "C1_1") (pintype "passive"))
      (node (ref "C73") (pin "1") (pinfunction "C1_1") (pintype "passive"))
      (node (ref "C77") (pin "2") (pinfunction "C2_2") (pintype "passive"))
      (node (ref "C78") (pin "2") (pinfunction "C2_2") (pintype "passive"))
      (node (ref "C79") (pin "2") (pinfunction "C2_2") (pintype "passive"))
      (node (ref "Q1") (pin "3") (pinfunction "V+_3") (pintype "power_in"))
      (node (ref "Q1") (pin "4") (pinfunction "V+_4") (pintype "power_in"))
      (node (ref "Q1") (pin "5") (pinfunction "V+_5") (pintype "power_in"))
      (node (ref "Q2") (pin "3") (pinfunction "V+_3") (pintype "power_in"))
      (node (ref "Q2") (pin "4") (pinfunction "V+_4") (pintype "power_in"))
      (node (ref "Q2") (pin "5") (pinfunction "V+_5") (pintype "power_in"))
      (node (ref "Q3") (pin "3") (pinfunction "V+_3") (pintype "power_in"))
      (node (ref "Q3") (pin "4") (pinfunction "V+_4") (pintype "power_in"))
      (node (ref "Q3") (pin "5") (pinfunction "V+_5") (pintype "power_in"))
      (node (ref "R58") (pin "1") (pinfunction "R1_1") (pintype "passive"))
      (node (ref "R65") (pin "1") (pinfunction "R1_1") (pintype "passive"))
      (node (ref "R72") (pin "1") (pinfunction "R1_1") (pintype "passive"))
      (node (ref "U14") (pin "25") (pinfunction "VSA_25") (pintype "power_in"))
      (node (ref "U14") (pin "28") (pinfunction "VS_28") (pintype "power_in"))
    )
    (net (code "69") (name "VDD") (class "Default")
      (node (ref "C74") (pin "1") (pinfunction "C1_1") (pintype "passive"))
      (node (ref "R38") (pin "2") (pinfunction "R2_2") (pintype "passive"))
      (node (ref "U14") (pin "16") (pinfunction "VCC_IO_16") (pintype "power_in"))
    )
  )
)
